# LM502_Break_Out_Board_v1_0.net
KiCad netlist of a schematic drawn in EAGLE
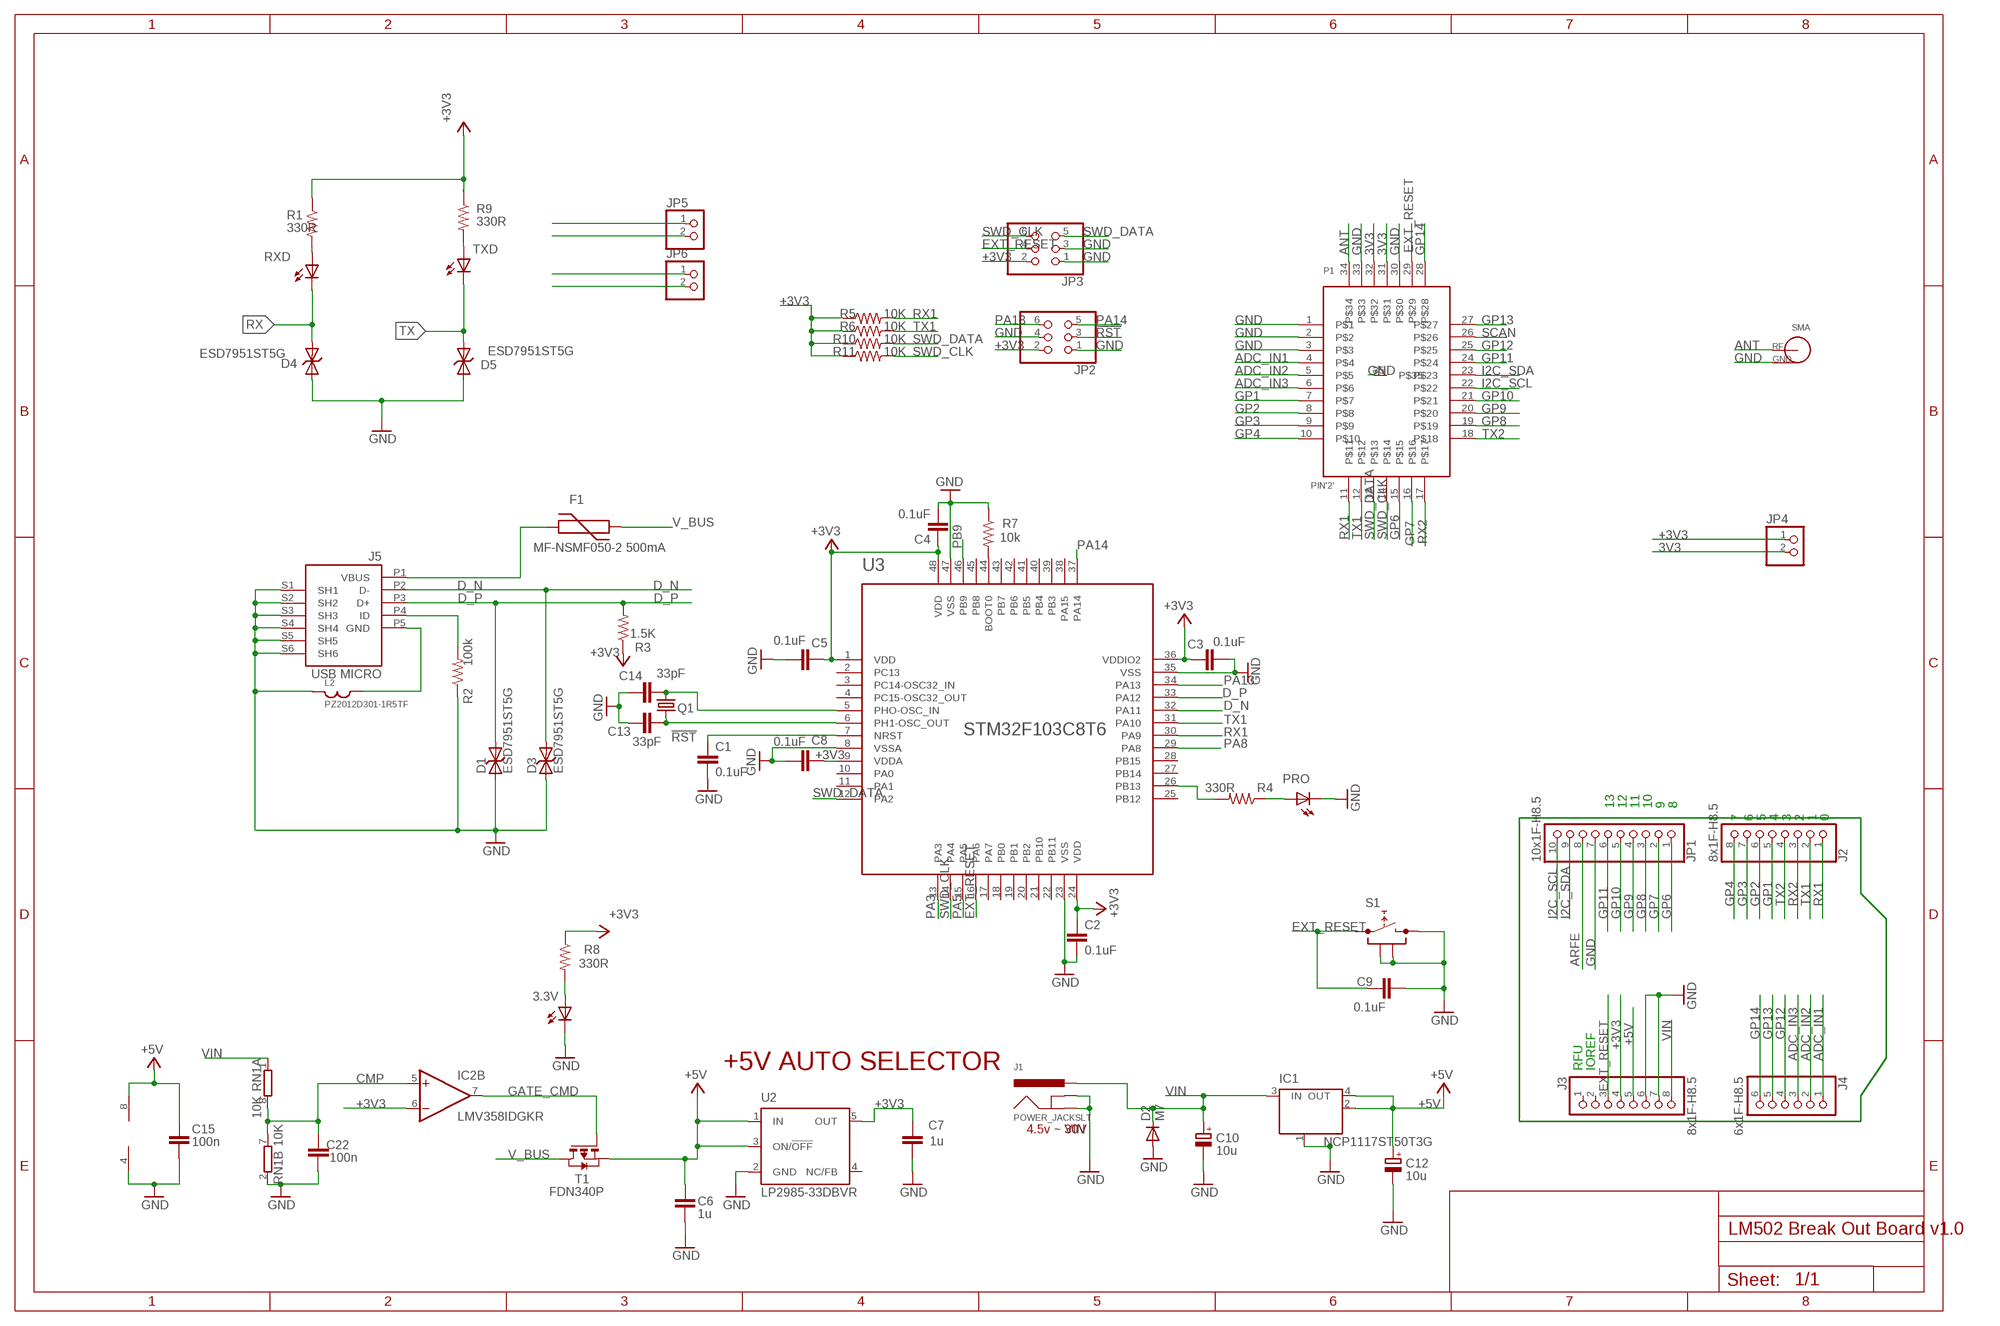
[diagram p0: schematic, sheet 1]

(export (version "E")
  (design (tool "Eeschema 10.0.6"))
  (components
    (comp (ref "3.3V")
      (value "LEDCHIP-LED0603")
      (footprint "eagle-import:CHIP-LED0603")
      (libsource (lib "eagle-import") (part "LEDCHIP-LED0603"))
    )
    (comp (ref "C1")
      (value "0.1uF")
      (footprint "eagle-import:C0402")
      (libsource (lib "eagle-import") (part "dragino-passive_C-EUC0402"))
    )
    (comp (ref "C2")
      (value "0.1uF")
      (footprint "eagle-import:C0402")
      (libsource (lib "eagle-import") (part "dragino-passive_C-EUC0402"))
    )
    (comp (ref "C3")
      (value "0.1uF")
      (footprint "eagle-import:C0402")
      (libsource (lib "eagle-import") (part "dragino-passive_C-EUC0402"))
    )
    (comp (ref "C4")
      (value "0.1uF")
      (footprint "eagle-import:C0402")
      (libsource (lib "eagle-import") (part "dragino-passive_C-EUC0402"))
    )
    (comp (ref "C5")
      (value "0.1uF")
      (footprint "eagle-import:C0402")
      (libsource (lib "eagle-import") (part "dragino-passive_C-EUC0402"))
    )
    (comp (ref "C6")
      (value "1u")
      (footprint "eagle-import:C0603-ROUND")
      (libsource (lib "eagle-import") (part "C-EUC0603"))
    )
    (comp (ref "C7")
      (value "1u")
      (footprint "eagle-import:C0603-ROUND")
      (libsource (lib "eagle-import") (part "C-EUC0603"))
    )
    (comp (ref "C8")
      (value "0.1uF")
      (footprint "eagle-import:C0402")
      (libsource (lib "eagle-import") (part "dragino-passive_C-EUC0402"))
    )
    (comp (ref "C9")
      (value "0.1uF")
      (footprint "eagle-import:C0402")
      (libsource (lib "eagle-import") (part "dragino-passive_C-EUC0402"))
    )
    (comp (ref "C10")
      (value "10u")
      (footprint "eagle-import:SMC_B")
      (libsource (lib "eagle-import") (part "CPOL-EUSMCB"))
    )
    (comp (ref "C12")
      (value "10u")
      (footprint "eagle-import:SMC_B")
      (libsource (lib "eagle-import") (part "CPOL-EUSMCB"))
    )
    (comp (ref "C13")
      (value "33pF")
      (footprint "eagle-import:C0402")
      (libsource (lib "eagle-import") (part "dragino-passive_C-EUC0402"))
    )
    (comp (ref "C14")
      (value "33pF")
      (footprint "eagle-import:C0402")
      (libsource (lib "eagle-import") (part "dragino-passive_C-EUC0402"))
    )
    (comp (ref "C15")
      (value "100n")
      (footprint "eagle-import:C0402")
      (libsource (lib "eagle-import") (part "C-EUC0402"))
    )
    (comp (ref "C22")
      (value "100n")
      (footprint "eagle-import:C0402")
      (libsource (lib "eagle-import") (part "C-EUC0402"))
    )
    (comp (ref "D1")
      (value "ESD7951ST5G")
      (footprint "eagle-import:SOD−923")
      (libsource (lib "eagle-import") (part "TVSSOD−923"))
    )
    (comp (ref "D2")
      (value "M7")
      (footprint "eagle-import:SMB")
      (libsource (lib "eagle-import") (part "DIODE-SMB"))
    )
    (comp (ref "D3")
      (value "ESD7951ST5G")
      (footprint "eagle-import:SOD−923")
      (libsource (lib "eagle-import") (part "TVSSOD−923"))
    )
    (comp (ref "D4")
      (value "ESD7951ST5G")
      (footprint "eagle-import:SOD−923")
      (libsource (lib "eagle-import") (part "TVSSOD−923"))
    )
    (comp (ref "D5")
      (value "ESD7951ST5G")
      (footprint "eagle-import:SOD−923")
      (libsource (lib "eagle-import") (part "TVSSOD−923"))
    )
    (comp (ref "F1")
      (value "MF-NSMF050-2 500mA")
      (footprint "eagle-import:R1206")
      (libsource (lib "eagle-import") (part "FUSE1206"))
    )
    (comp (ref "IC1")
      (value "NCP1117ST50T3G")
      (footprint "eagle-import:SOT223")
      (libsource (lib "eagle-import") (part "MC33269ST-3.3T3"))
    )
    (comp (ref "IC2")
      (value "LMV358IDGKR")
      (footprint "eagle-import:MSOP08")
      (libsource (lib "eagle-import") (part "LMV358?MMX"))
    )
    (comp (ref "J1")
      (value "POWER_JACKSLT")
      (footprint "eagle-import:POWER_JACK_SLOT")
      (libsource (lib "eagle-import") (part "POWER_JACKSLT"))
    )
    (comp (ref "J2")
      (value "8x1F-H8.5")
      (footprint "eagle-import:1X08")
      (libsource (lib "eagle-import") (part "PINHD-1X8"))
    )
    (comp (ref "J3")
      (value "8x1F-H8.5")
      (footprint "eagle-import:1X08")
      (libsource (lib "eagle-import") (part "PINHD-1X8"))
    )
    (comp (ref "J4")
      (value "6x1F-H8.5")
      (footprint "eagle-import:1X06")
      (libsource (lib "eagle-import") (part "PINHD-1X6"))
    )
    (comp (ref "J5")
      (value "USB MICRO")
      (footprint "eagle-import:CON2_USB_MICRO_B_AT")
      (libsource (lib "eagle-import") (part "MYCON2_USB-MINI-B"))
    )
    (comp (ref "JP1")
      (value "10x1F-H8.5")
      (footprint "eagle-import:1X10")
      (libsource (lib "eagle-import") (part "PINHD-1X10"))
    )
    (comp (ref "JP2")
      (value "PINHD-2X3")
      (footprint "eagle-import:2X3-2.0")
      (libsource (lib "eagle-import") (part "PINHD-2X3"))
    )
    (comp (ref "JP3")
      (value "PINHD-2X3'2'")
      (footprint "eagle-import:2X03")
      (libsource (lib "eagle-import") (part "PINHD-2X3'2'"))
    )
    (comp (ref "JP4")
      (value "PINHD-1X2")
      (footprint "eagle-import:1X02")
      (libsource (lib "eagle-import") (part "PINHD-1X2"))
    )
    (comp (ref "JP5")
      (value "PINHD-1X2")
      (footprint "eagle-import:1X02")
      (libsource (lib "eagle-import") (part "PINHD-1X2"))
    )
    (comp (ref "JP6")
      (value "PINHD-1X2")
      (footprint "eagle-import:1X02")
      (libsource (lib "eagle-import") (part "PINHD-1X2"))
    )
    (comp (ref "L2")
      (value "PZ2012D301-1R5TF")
      (footprint "eagle-import:C0805@1")
      (libsource (lib "eagle-import") (part "BEADS0805"))
    )
    (comp (ref "P1")
      (value "PIN'2'")
      (footprint "eagle-import:LM502")
      (libsource (lib "eagle-import") (part "PIN'2'"))
    )
    (comp (ref "PRO")
      (value "LEDCHIP-LED0603")
      (footprint "eagle-import:CHIP-LED0603")
      (libsource (lib "eagle-import") (part "LEDCHIP-LED0603"))
    )
    (comp (ref "Q1")
      (value "CRYSTALHC49S")
      (footprint "eagle-import:HC49_S")
      (libsource (lib "eagle-import") (part "CRYSTALHC49S"))
    )
    (comp (ref "R1")
      (value "330R")
      (footprint "eagle-import:R0402")
      (libsource (lib "eagle-import") (part "R-US_R0402"))
    )
    (comp (ref "R2")
      (value "100k")
      (footprint "eagle-import:R0402")
      (libsource (lib "eagle-import") (part "R-US_R0402"))
    )
    (comp (ref "R3")
      (value "1.5K")
      (footprint "eagle-import:R0402")
      (libsource (lib "eagle-import") (part "R-US_R0402"))
    )
    (comp (ref "R4")
      (value "330R")
      (footprint "eagle-import:R0402")
      (libsource (lib "eagle-import") (part "R-US_R0402"))
    )
    (comp (ref "R5")
      (value "10K")
      (footprint "eagle-import:R0402")
      (libsource (lib "eagle-import") (part "R-US_R0402"))
    )
    (comp (ref "R6")
      (value "10K")
      (footprint "eagle-import:R0402")
      (libsource (lib "eagle-import") (part "R-US_R0402"))
    )
    (comp (ref "R7")
      (value "10k")
      (footprint "eagle-import:R0402")
      (libsource (lib "eagle-import") (part "R-US_R0402"))
    )
    (comp (ref "R8")
      (value "330R")
      (footprint "eagle-import:R0402")
      (libsource (lib "eagle-import") (part "R-US_R0402"))
    )
    (comp (ref "R9")
      (value "330R")
      (footprint "eagle-import:R0402")
      (libsource (lib "eagle-import") (part "R-US_R0402"))
    )
    (comp (ref "R10")
      (value "10K")
      (footprint "eagle-import:R0402")
      (libsource (lib "eagle-import") (part "R-US_R0402"))
    )
    (comp (ref "R11")
      (value "10K")
      (footprint "eagle-import:R0402")
      (libsource (lib "eagle-import") (part "R-US_R0402"))
    )
    (comp (ref "RN1")
      (value "10K")
      (footprint "eagle-import:CAY16")
      (libsource (lib "eagle-import") (part "4R-NCAY16"))
    )
    (comp (ref "RXD")
      (value "LEDCHIP-LED0603")
      (footprint "eagle-import:CHIP-LED0603")
      (libsource (lib "eagle-import") (part "LEDCHIP-LED0603"))
    )
    (comp (ref "S1")
      (value "PUSH_SWITCH")
      (footprint "eagle-import:SWITCH_6X6X5")
      (libsource (lib "eagle-import") (part "PUSH_SWITCH"))
    )
    (comp (ref "SMA")
      (value "SMA-KWE")
      (footprint "eagle-import:SMA-KWE")
      (libsource (lib "eagle-import") (part "SMA-KWE"))
    )
    (comp (ref "T1")
      (value "FDN340P")
      (footprint "eagle-import:SOT-23")
      (libsource (lib "eagle-import") (part "PMOSSOT23"))
    )
    (comp (ref "TXD")
      (value "LEDCHIP-LED0603")
      (footprint "eagle-import:CHIP-LED0603")
      (libsource (lib "eagle-import") (part "LEDCHIP-LED0603"))
    )
    (comp (ref "U2")
      (value "LP2985-33DBVR")
      (footprint "eagle-import:SOT23-DBV")
      (libsource (lib "eagle-import") (part "LP2985-XXDBVR33"))
    )
    (comp (ref "U3")
      (value "STM32F103C8T6")
      (footprint "eagle-import:LQFP48")
      (libsource (lib "eagle-import") (part "STM32L0XX"))
    )
  )
  (nets
    (net (code "1") (name "+3V3") (class "Default")
      (node (ref "C2") (pin "1") (pinfunction "1_1") (pintype "passive"))
      (node (ref "C3") (pin "1") (pinfunction "1_1") (pintype "passive"))
      (node (ref "C4") (pin "1") (pinfunction "1_1") (pintype "passive"))
      (node (ref "C5") (pin "1") (pinfunction "1_1") (pintype "passive"))
      (node (ref "C7") (pin "2") (pinfunction "2_2") (pintype "passive"))
      (node (ref "C8") (pin "1") (pinfunction "1_1") (pintype "passive"))
      (node (ref "IC2") (pin "6") (pinfunction "-IN_6") (pintype "input"))
      (node (ref "J3") (pin "4") (pinfunction "4_4") (pintype "passive"))
      (node (ref "JP2") (pin "2") (pinfunction "2_2") (pintype "passive"))
      (node (ref "JP3") (pin "2") (pinfunction "2_2") (pintype "passive"))
      (node (ref "JP4") (pin "1") (pinfunction "1_1") (pintype "passive"))
      (node (ref "R1") (pin "1") (pinfunction "1_1") (pintype "passive"))
      (node (ref "R10") (pin "1") (pinfunction "1_1") (pintype "passive"))
      (node (ref "R11") (pin "1") (pinfunction "1_1") (pintype "passive"))
      (node (ref "R3") (pin "1") (pinfunction "1_1") (pintype "passive"))
      (node (ref "R5") (pin "1") (pinfunction "1_1") (pintype "passive"))
      (node (ref "R6") (pin "1") (pinfunction "1_1") (pintype "passive"))
      (node (ref "R8") (pin "1") (pinfunction "1_1") (pintype "passive"))
      (node (ref "R9") (pin "1") (pinfunction "1_1") (pintype "passive"))
      (node (ref "U2") (pin "5") (pinfunction "OUT_5") (pintype "passive"))
      (node (ref "U3") (pin "1") (pinfunction "VDD_1") (pintype "bidirectional"))
      (node (ref "U3") (pin "24") (pinfunction "VDD_24") (pintype "bidirectional"))
      (node (ref "U3") (pin "36") (pinfunction "VDDIO2_36") (pintype "bidirectional"))
      (node (ref "U3") (pin "48") (pinfunction "VDD_48") (pintype "bidirectional"))
      (node (ref "U3") (pin "9") (pinfunction "VDDA_9") (pintype "bidirectional"))
    )
    (net (code "2") (name "+5V") (class "Default")
      (node (ref "C12") (pin "+") (pinfunction "+_+") (pintype "passive"))
      (node (ref "C15") (pin "1") (pinfunction "1_1") (pintype "passive"))
      (node (ref "C6") (pin "2") (pinfunction "2_2") (pintype "passive"))
      (node (ref "IC1") (pin "2") (pinfunction "OUT_2") (pintype "passive"))
      (node (ref "IC1") (pin "4") (pinfunction "OUT_4") (pintype "passive"))
      (node (ref "IC2") (pin "8") (pinfunction "V+_8") (pintype "power_in"))
      (node (ref "J3") (pin "5") (pinfunction "5_5") (pintype "passive"))
      (node (ref "T1") (pin "2") (pinfunction "S_2") (pintype "passive"))
      (node (ref "U2") (pin "1") (pinfunction "IN_1") (pintype "input"))
      (node (ref "U2") (pin "3") (pinfunction "ON/~{OFF}_3") (pintype "input"))
    )
    (net (code "3") (name "/3V3") (class "Default")
      (node (ref "JP4") (pin "2") (pinfunction "2_2") (pintype "passive"))
      (node (ref "P1") (pin "31") (pinfunction "P$31_31") (pintype "bidirectional"))
      (node (ref "P1") (pin "32") (pinfunction "P$32_32") (pintype "bidirectional"))
    )
    (net (code "4") (name "/ADC_IN1") (class "Default")
      (node (ref "J4") (pin "1") (pinfunction "1_1") (pintype "passive"))
      (node (ref "P1") (pin "4") (pinfunction "P$4_4") (pintype "bidirectional"))
    )
    (net (code "5") (name "/ADC_IN2") (class "Default")
      (node (ref "J4") (pin "2") (pinfunction "2_2") (pintype "passive"))
      (node (ref "P1") (pin "5") (pinfunction "P$5_5") (pintype "bidirectional"))
    )
    (net (code "6") (name "/ADC_IN3") (class "Default")
      (node (ref "J4") (pin "3") (pinfunction "3_3") (pintype "passive"))
      (node (ref "P1") (pin "6") (pinfunction "P$6_6") (pintype "bidirectional"))
    )
    (net (code "7") (name "/ANT") (class "Default")
      (node (ref "P1") (pin "34") (pinfunction "P$34_34") (pintype "bidirectional"))
      (node (ref "SMA") (pin "1") (pinfunction "SIG_1") (pintype "passive"))
    )
    (net (code "8") (name "/ARFE") (class "Default")
      (node (ref "JP1") (pin "8") (pinfunction "8_8") (pintype "passive"))
    )
    (net (code "9") (name "/CMP") (class "Default")
      (node (ref "C22") (pin "2") (pinfunction "2_2") (pintype "passive"))
      (node (ref "IC2") (pin "5") (pinfunction "+IN_5") (pintype "input"))
      (node (ref "RN1") (pin "7") (pinfunction "2_7") (pintype "passive"))
      (node (ref "RN1") (pin "8") (pinfunction "2_8") (pintype "passive"))
    )
    (net (code "10") (name "/D_N") (class "Default")
      (node (ref "D3") (pin "P$2") (pinfunction "2_P$2") (pintype "passive"))
      (node (ref "J5") (pin "P2") (pinfunction "D-_P2") (pintype "bidirectional"))
      (node (ref "U3") (pin "32") (pinfunction "PA11_32") (pintype "bidirectional"))
    )
    (net (code "11") (name "/D_P") (class "Default")
      (node (ref "D1") (pin "P$2") (pinfunction "2_P$2") (pintype "passive"))
      (node (ref "J5") (pin "P3") (pinfunction "D+_P3") (pintype "bidirectional"))
      (node (ref "R3") (pin "2") (pinfunction "2_2") (pintype "passive"))
      (node (ref "U3") (pin "33") (pinfunction "PA12_33") (pintype "bidirectional"))
    )
    (net (code "12") (name "/EXT_RESET") (class "Default")
      (node (ref "C9") (pin "1") (pinfunction "1_1") (pintype "passive"))
      (node (ref "J3") (pin "3") (pinfunction "3_3") (pintype "passive"))
      (node (ref "JP3") (pin "4") (pinfunction "4_4") (pintype "passive"))
      (node (ref "P1") (pin "29") (pinfunction "P$29_29") (pintype "bidirectional"))
      (node (ref "S1") (pin "1") (pinfunction "1_1") (pintype "passive"))
      (node (ref "U3") (pin "16") (pinfunction "PA6_16") (pintype "bidirectional"))
    )
    (net (code "13") (name "/GATE_CMD") (class "Default")
      (node (ref "IC2") (pin "7") (pinfunction "OUT_7") (pintype "output"))
      (node (ref "T1") (pin "3") (pinfunction "G_3") (pintype "passive"))
    )
    (net (code "14") (name "/GP1") (class "Default")
      (node (ref "J2") (pin "5") (pinfunction "5_5") (pintype "passive"))
      (node (ref "P1") (pin "7") (pinfunction "P$7_7") (pintype "bidirectional"))
    )
    (net (code "15") (name "/GP2") (class "Default")
      (node (ref "J2") (pin "6") (pinfunction "6_6") (pintype "passive"))
      (node (ref "P1") (pin "8") (pinfunction "P$8_8") (pintype "bidirectional"))
    )
    (net (code "16") (name "/GP3") (class "Default")
      (node (ref "J2") (pin "7") (pinfunction "7_7") (pintype "passive"))
      (node (ref "P1") (pin "9") (pinfunction "P$9_9") (pintype "bidirectional"))
    )
    (net (code "17") (name "/GP4") (class "Default")
      (node (ref "J2") (pin "8") (pinfunction "8_8") (pintype "passive"))
      (node (ref "P1") (pin "10") (pinfunction "P$10_10") (pintype "bidirectional"))
    )
    (net (code "18") (name "/GP6") (class "Default")
      (node (ref "JP1") (pin "1") (pinfunction "1_1") (pintype "passive"))
      (node (ref "P1") (pin "15") (pinfunction "P$15_15") (pintype "bidirectional"))
    )
    (net (code "19") (name "/GP7") (class "Default")
      (node (ref "JP1") (pin "2") (pinfunction "2_2") (pintype "passive"))
      (node (ref "P1") (pin "16") (pinfunction "P$16_16") (pintype "bidirectional"))
    )
    (net (code "20") (name "/GP8") (class "Default")
      (node (ref "JP1") (pin "3") (pinfunction "3_3") (pintype "passive"))
      (node (ref "P1") (pin "19") (pinfunction "P$19_19") (pintype "bidirectional"))
    )
    (net (code "21") (name "/GP9") (class "Default")
      (node (ref "JP1") (pin "4") (pinfunction "4_4") (pintype "passive"))
      (node (ref "P1") (pin "20") (pinfunction "P$20_20") (pintype "bidirectional"))
    )
    (net (code "22") (name "/GP10") (class "Default")
      (node (ref "JP1") (pin "5") (pinfunction "5_5") (pintype "passive"))
      (node (ref "P1") (pin "21") (pinfunction "P$21_21") (pintype "bidirectional"))
    )
    (net (code "23") (name "/GP11") (class "Default")
      (node (ref "JP1") (pin "6") (pinfunction "6_6") (pintype "passive"))
      (node (ref "P1") (pin "24") (pinfunction "P$24_24") (pintype "bidirectional"))
    )
    (net (code "24") (name "/GP12") (class "Default")
      (node (ref "J4") (pin "4") (pinfunction "4_4") (pintype "passive"))
      (node (ref "P1") (pin "25") (pinfunction "P$25_25") (pintype "bidirectional"))
    )
    (net (code "25") (name "/GP13") (class "Default")
      (node (ref "J4") (pin "5") (pinfunction "5_5") (pintype "passive"))
      (node (ref "P1") (pin "27") (pinfunction "P$27_27") (pintype "bidirectional"))
    )
    (net (code "26") (name "/GP14") (class "Default")
      (node (ref "J4") (pin "6") (pinfunction "6_6") (pintype "passive"))
      (node (ref "P1") (pin "28") (pinfunction "P$28_28") (pintype "bidirectional"))
    )
    (net (code "27") (name "/I2C_SCL") (class "Default")
      (node (ref "JP1") (pin "10") (pinfunction "10_10") (pintype "passive"))
      (node (ref "P1") (pin "22") (pinfunction "P$22_22") (pintype "bidirectional"))
    )
    (net (code "28") (name "/I2C_SDA") (class "Default")
      (node (ref "JP1") (pin "9") (pinfunction "9_9") (pintype "passive"))
      (node (ref "P1") (pin "23") (pinfunction "P$23_23") (pintype "bidirectional"))
    )
    (net (code "29") (name "/PA3") (class "Default")
      (node (ref "U3") (pin "13") (pinfunction "PA3_13") (pintype "bidirectional"))
    )
    (net (code "30") (name "/PA5") (class "Default")
      (node (ref "U3") (pin "15") (pinfunction "PA5_15") (pintype "bidirectional"))
    )
    (net (code "31") (name "/PA8") (class "Default")
      (node (ref "U3") (pin "29") (pinfunction "PA8_29") (pintype "bidirectional"))
    )
    (net (code "32") (name "/PA13") (class "Default")
      (node (ref "JP2") (pin "6") (pinfunction "6_6") (pintype "passive"))
      (node (ref "U3") (pin "34") (pinfunction "PA13_34") (pintype "bidirectional"))
    )
    (net (code "33") (name "/PA14") (class "Default")
      (node (ref "JP2") (pin "5") (pinfunction "5_5") (pintype "passive"))
      (node (ref "U3") (pin "37") (pinfunction "PA14_37") (pintype "bidirectional"))
    )
    (net (code "34") (name "/PB9") (class "Default")
      (node (ref "U3") (pin "46") (pinfunction "PB9_46") (pintype "bidirectional"))
    )
    (net (code "35") (name "/RX1") (class "Default")
      (node (ref "J2") (pin "1") (pinfunction "1_1") (pintype "passive"))
      (node (ref "JP5") (pin "2") (pinfunction "2_2") (pintype "passive"))
      (node (ref "P1") (pin "11") (pinfunction "P$11_11") (pintype "bidirectional"))
      (node (ref "R5") (pin "2") (pinfunction "2_2") (pintype "passive"))
      (node (ref "U3") (pin "30") (pinfunction "PA9_30") (pintype "bidirectional"))
    )
    (net (code "36") (name "/RX2") (class "Default")
      (node (ref "J2") (pin "3") (pinfunction "3_3") (pintype "passive"))
      (node (ref "P1") (pin "17") (pinfunction "P$17_17") (pintype "bidirectional"))
    )
    (net (code "37") (name "/SCAN") (class "Default")
      (node (ref "P1") (pin "26") (pinfunction "P$26_26") (pintype "bidirectional"))
    )
    (net (code "38") (name "/SWD_CLK") (class "Default")
      (node (ref "JP3") (pin "6") (pinfunction "6_6") (pintype "passive"))
      (node (ref "P1") (pin "14") (pinfunction "P$14_14") (pintype "bidirectional"))
      (node (ref "R11") (pin "2") (pinfunction "2_2") (pintype "passive"))
      (node (ref "U3") (pin "14") (pinfunction "PA4_14") (pintype "bidirectional"))
    )
    (net (code "39") (name "/SWD_DATA") (class "Default")
      (node (ref "JP3") (pin "5") (pinfunction "5_5") (pintype "passive"))
      (node (ref "P1") (pin "13") (pinfunction "P$13_13") (pintype "bidirectional"))
      (node (ref "R10") (pin "2") (pinfunction "2_2") (pintype "passive"))
      (node (ref "U3") (pin "12") (pinfunction "PA2_12") (pintype "bidirectional"))
    )
    (net (code "40") (name "/TX1") (class "Default")
      (node (ref "J2") (pin "2") (pinfunction "2_2") (pintype "passive"))
      (node (ref "JP6") (pin "1") (pinfunction "1_1") (pintype "passive"))
      (node (ref "P1") (pin "12") (pinfunction "P$12_12") (pintype "bidirectional"))
      (node (ref "R6") (pin "2") (pinfunction "2_2") (pintype "passive"))
      (node (ref "U3") (pin "31") (pinfunction "PA10_31") (pintype "bidirectional"))
    )
    (net (code "41") (name "/TX2") (class "Default")
      (node (ref "J2") (pin "4") (pinfunction "4_4") (pintype "passive"))
      (node (ref "P1") (pin "18") (pinfunction "P$18_18") (pintype "bidirectional"))
    )
    (net (code "42") (name "/VIN") (class "Default")
      (node (ref "C10") (pin "+") (pinfunction "+_+") (pintype "passive"))
      (node (ref "D2") (pin "C") (pinfunction "C_C") (pintype "passive"))
      (node (ref "IC1") (pin "3") (pinfunction "IN_3") (pintype "input"))
      (node (ref "J1") (pin "PWR") (pinfunction "PWR_PWR") (pintype "bidirectional"))
      (node (ref "J3") (pin "8") (pinfunction "8_8") (pintype "passive"))
      (node (ref "RN1") (pin "1") (pinfunction "1_1") (pintype "passive"))
    )
    (net (code "43") (name "/V_BUS") (class "Default")
      (node (ref "F1") (pin "1") (pinfunction "1_1") (pintype "passive"))
      (node (ref "T1") (pin "1") (pinfunction "D_1") (pintype "passive"))
    )
    (net (code "44") (name "/~{RST}") (class "Default")
      (node (ref "C1") (pin "1") (pinfunction "1_1") (pintype "passive"))
      (node (ref "JP2") (pin "3") (pinfunction "3_3") (pintype "passive"))
      (node (ref "U3") (pin "7") (pinfunction "NRST_7") (pintype "bidirectional"))
    )
    (net (code "45") (name "GND") (class "Default")
      (node (ref "3.3V") (pin "C") (pinfunction "C_C") (pintype "passive"))
      (node (ref "C1") (pin "2") (pinfunction "2_2") (pintype "passive"))
      (node (ref "C10") (pin "-") (pinfunction "-_-") (pintype "passive"))
      (node (ref "C12") (pin "-") (pinfunction "-_-") (pintype "passive"))
      (node (ref "C13") (pin "1") (pinfunction "1_1") (pintype "passive"))
      (node (ref "C14") (pin "1") (pinfunction "1_1") (pintype "passive"))
      (node (ref "C15") (pin "2") (pinfunction "2_2") (pintype "passive"))
      (node (ref "C2") (pin "2") (pinfunction "2_2") (pintype "passive"))
      (node (ref "C22") (pin "1") (pinfunction "1_1") (pintype "passive"))
      (node (ref "C3") (pin "2") (pinfunction "2_2") (pintype "passive"))
      (node (ref "C4") (pin "2") (pinfunction "2_2") (pintype "passive"))
      (node (ref "C5") (pin "2") (pinfunction "2_2") (pintype "passive"))
      (node (ref "C6") (pin "1") (pinfunction "1_1") (pintype "passive"))
      (node (ref "C7") (pin "1") (pinfunction "1_1") (pintype "passive"))
      (node (ref "C8") (pin "2") (pinfunction "2_2") (pintype "passive"))
      (node (ref "C9") (pin "2") (pinfunction "2_2") (pintype "passive"))
      (node (ref "D1") (pin "P$1") (pinfunction "1_P$1") (pintype "passive"))
      (node (ref "D2") (pin "A") (pinfunction "A_A") (pintype "passive"))
      (node (ref "D3") (pin "P$1") (pinfunction "1_P$1") (pintype "passive"))
      (node (ref "D4") (pin "P$1") (pinfunction "1_P$1") (pintype "passive"))
      (node (ref "D5") (pin "P$1") (pinfunction "1_P$1") (pintype "passive"))
      (node (ref "IC1") (pin "1") (pinfunction "GND/ADJ_1") (pintype "input"))
      (node (ref "IC2") (pin "4") (pinfunction "V-_4") (pintype "power_in"))
      (node (ref "J1") (pin "GND@1") (pinfunction "GNDBREAK_GND@1") (pintype "bidirectional"))
      (node (ref "J1") (pin "GND@2") (pinfunction "GND_GND@2") (pintype "bidirectional"))
      (node (ref "J3") (pin "6") (pinfunction "6_6") (pintype "passive"))
      (node (ref "J3") (pin "7") (pinfunction "7_7") (pintype "passive"))
      (node (ref "J5") (pin "S1") (pinfunction "SH1_S1") (pintype "passive"))
      (node (ref "J5") (pin "S2") (pinfunction "SH2_S2") (pintype "passive"))
      (node (ref "J5") (pin "S3") (pinfunction "SH3_S3") (pintype "passive"))
      (node (ref "J5") (pin "S4") (pinfunction "SH4_S4") (pintype "passive"))
      (node (ref "J5") (pin "S5") (pinfunction "SH5_S5") (pintype "passive"))
      (node (ref "J5") (pin "S6") (pinfunction "SH6_S6") (pintype "passive"))
      (node (ref "JP1") (pin "7") (pinfunction "7_7") (pintype "passive"))
      (node (ref "JP2") (pin "1") (pinfunction "1_1") (pintype "passive"))
      (node (ref "JP2") (pin "4") (pinfunction "4_4") (pintype "passive"))
      (node (ref "JP3") (pin "1") (pinfunction "1_1") (pintype "passive"))
      (node (ref "JP3") (pin "3") (pinfunction "3_3") (pintype "passive"))
      (node (ref "L2") (pin "1") (pinfunction "P$1_1") (pintype "bidirectional"))
      (node (ref "P1") (pin "1") (pinfunction "P$1_1") (pintype "bidirectional"))
      (node (ref "P1") (pin "2") (pinfunction "P$2_2") (pintype "bidirectional"))
      (node (ref "P1") (pin "3") (pinfunction "P$3_3") (pintype "bidirectional"))
      (node (ref "P1") (pin "30") (pinfunction "P$30_30") (pintype "bidirectional"))
      (node (ref "P1") (pin "33") (pinfunction "P$33_33") (pintype "bidirectional"))
      (node (ref "P1") (pin "35") (pinfunction "P$35_35") (pintype "bidirectional"))
      (node (ref "PRO") (pin "C") (pinfunction "C_C") (pintype "passive"))
      (node (ref "R2") (pin "1") (pinfunction "1_1") (pintype "passive"))
      (node (ref "R7") (pin "1") (pinfunction "1_1") (pintype "passive"))
      (node (ref "RN1") (pin "2") (pinfunction "1_2") (pintype "passive"))
      (node (ref "S1") (pin "2") (pinfunction "2_2") (pintype "passive"))
      (node (ref "S1") (pin "3") (pinfunction "3_3") (pintype "passive"))
      (node (ref "S1") (pin "4") (pinfunction "4_4") (pintype "passive"))
      (node (ref "SMA") (pin "2") (pinfunction "GND_2") (pintype "passive"))
      (node (ref "SMA") (pin "3") (pinfunction "GND_3") (pintype "passive"))
      (node (ref "SMA") (pin "4") (pinfunction "GND_4") (pintype "passive"))
      (node (ref "SMA") (pin "5") (pinfunction "GND_5") (pintype "passive"))
      (node (ref "U2") (pin "2") (pinfunction "GND_2") (pintype "power_in"))
      (node (ref "U3") (pin "23") (pinfunction "VSS_23") (pintype "bidirectional"))
      (node (ref "U3") (pin "35") (pinfunction "VSS_35") (pintype "bidirectional"))
      (node (ref "U3") (pin "47") (pinfunction "VSS_47") (pintype "bidirectional"))
      (node (ref "U3") (pin "8") (pinfunction "VSSA_8") (pintype "bidirectional"))
    )
    (net (code "46") (name "Net-(3.3V-PadA)") (class "Default")
      (node (ref "3.3V") (pin "A") (pinfunction "A_A") (pintype "passive"))
      (node (ref "R8") (pin "2") (pinfunction "2_2") (pintype "passive"))
    )
    (net (code "47") (name "Net-(J5-GND)") (class "Default")
      (node (ref "J5") (pin "P5") (pinfunction "GND_P5") (pintype "passive"))
      (node (ref "L2") (pin "2") (pinfunction "P$2_2") (pintype "bidirectional"))
    )
    (net (code "48") (name "Net-(J5-ID)") (class "Default")
      (node (ref "J5") (pin "P4") (pinfunction "ID_P4") (pintype "bidirectional"))
      (node (ref "R2") (pin "2") (pinfunction "2_2") (pintype "passive"))
    )
    (net (code "49") (name "Net-(J5-VBUS)") (class "Default")
      (node (ref "F1") (pin "2") (pinfunction "2_2") (pintype "passive"))
      (node (ref "J5") (pin "P1") (pinfunction "VBUS_P1") (pintype "power_in"))
    )
    (net (code "50") (name "Net-(PRO-PadA)") (class "Default")
      (node (ref "PRO") (pin "A") (pinfunction "A_A") (pintype "passive"))
      (node (ref "R4") (pin "1") (pinfunction "1_1") (pintype "passive"))
    )
    (net (code "51") (name "Net-(R1-Pad2)") (class "Default")
      (node (ref "R1") (pin "2") (pinfunction "2_2") (pintype "passive"))
      (node (ref "RXD") (pin "A") (pinfunction "A_A") (pintype "passive"))
    )
    (net (code "52") (name "Net-(R9-Pad2)") (class "Default")
      (node (ref "R9") (pin "2") (pinfunction "2_2") (pintype "passive"))
      (node (ref "TXD") (pin "A") (pinfunction "A_A") (pintype "passive"))
    )
    (net (code "53") (name "Net-(U3-BOOT0)") (class "Default")
      (node (ref "R7") (pin "2") (pinfunction "2_2") (pintype "passive"))
      (node (ref "U3") (pin "44") (pinfunction "BOOT0_44") (pintype "bidirectional"))
    )
    (net (code "54") (name "Net-(U3-PB13)") (class "Default")
      (node (ref "R4") (pin "2") (pinfunction "2_2") (pintype "passive"))
      (node (ref "U3") (pin "26") (pinfunction "PB13_26") (pintype "bidirectional"))
    )
    (net (code "55") (name "Net-(U3-PH1-OSC_OUT)") (class "Default")
      (node (ref "C13") (pin "2") (pinfunction "2_2") (pintype "passive"))
      (node (ref "Q1") (pin "1") (pinfunction "1_1") (pintype "passive"))
      (node (ref "U3") (pin "6") (pinfunction "PH1-OSC_OUT_6") (pintype "bidirectional"))
    )
    (net (code "56") (name "Net-(U3-PHO-OSC_IN)") (class "Default")
      (node (ref "C14") (pin "2") (pinfunction "2_2") (pintype "passive"))
      (node (ref "Q1") (pin "2") (pinfunction "2_2") (pintype "passive"))
      (node (ref "U3") (pin "5") (pinfunction "PHO-OSC_IN_5") (pintype "bidirectional"))
    )
    (net (code "57") (name "RX") (class "Default")
      (node (ref "D4") (pin "P$2") (pinfunction "2_P$2") (pintype "passive"))
      (node (ref "JP5") (pin "1") (pinfunction "1_1") (pintype "passive"))
      (node (ref "RXD") (pin "C") (pinfunction "C_C") (pintype "passive"))
    )
    (net (code "58") (name "TX") (class "Default")
      (node (ref "D5") (pin "P$2") (pinfunction "2_P$2") (pintype "passive"))
      (node (ref "JP6") (pin "2") (pinfunction "2_2") (pintype "passive"))
      (node (ref "TXD") (pin "C") (pinfunction "C_C") (pintype "passive"))
    )
    (net (code "59") (name "unconnected-(J3-Pad1)") (class "Default")
      (node (ref "J3") (pin "1") (pinfunction "1_1") (pintype "passive"))
    )
    (net (code "60") (name "unconnected-(J3-Pad2)") (class "Default")
      (node (ref "J3") (pin "2") (pinfunction "2_2") (pintype "passive"))
    )
    (net (code "61") (name "unconnected-(U2-NC{slash}FB-Pad4)") (class "Default")
      (node (ref "U2") (pin "4") (pinfunction "NC/FB_4") (pintype "passive"))
    )
    (net (code "62") (name "unconnected-(U3-PA0-Pad10)") (class "Default")
      (node (ref "U3") (pin "10") (pinfunction "PA0_10") (pintype "bidirectional"))
    )
    (net (code "63") (name "unconnected-(U3-PA1-Pad11)") (class "Default")
      (node (ref "U3") (pin "11") (pinfunction "PA1_11") (pintype "bidirectional"))
    )
    (net (code "64") (name "unconnected-(U3-PA7-Pad17)") (class "Default")
      (node (ref "U3") (pin "17") (pinfunction "PA7_17") (pintype "bidirectional"))
    )
    (net (code "65") (name "unconnected-(U3-PA15-Pad38)") (class "Default")
      (node (ref "U3") (pin "38") (pinfunction "PA15_38") (pintype "bidirectional"))
    )
    (net (code "66") (name "unconnected-(U3-PB0-Pad18)") (class "Default")
      (node (ref "U3") (pin "18") (pinfunction "PB0_18") (pintype "bidirectional"))
    )
    (net (code "67") (name "unconnected-(U3-PB1-Pad19)") (class "Default")
      (node (ref "U3") (pin "19") (pinfunction "PB1_19") (pintype "bidirectional"))
    )
    (net (code "68") (name "unconnected-(U3-PB2-Pad20)") (class "Default")
      (node (ref "U3") (pin "20") (pinfunction "PB2_20") (pintype "bidirectional"))
    )
    (net (code "69") (name "unconnected-(U3-PB3-Pad39)") (class "Default")
      (node (ref "U3") (pin "39") (pinfunction "PB3_39") (pintype "bidirectional"))
    )
    (net (code "70") (name "unconnected-(U3-PB4-Pad40)") (class "Default")
      (node (ref "U3") (pin "40") (pinfunction "PB4_40") (pintype "bidirectional"))
    )
    (net (code "71") (name "unconnected-(U3-PB5-Pad41)") (class "Default")
      (node (ref "U3") (pin "41") (pinfunction "PB5_41") (pintype "bidirectional"))
    )
    (net (code "72") (name "unconnected-(U3-PB6-Pad42)") (class "Default")
      (node (ref "U3") (pin "42") (pinfunction "PB6_42") (pintype "bidirectional"))
    )
    (net (code "73") (name "unconnected-(U3-PB7-Pad43)") (class "Default")
      (node (ref "U3") (pin "43") (pinfunction "PB7_43") (pintype "bidirectional"))
    )
    (net (code "74") (name "unconnected-(U3-PB8-Pad45)") (class "Default")
      (node (ref "U3") (pin "45") (pinfunction "PB8_45") (pintype "bidirectional"))
    )
    (net (code "75") (name "unconnected-(U3-PB10-Pad21)") (class "Default")
      (node (ref "U3") (pin "21") (pinfunction "PB10_21") (pintype "bidirectional"))
    )
    (net (code "76") (name "unconnected-(U3-PB11-Pad22)") (class "Default")
      (node (ref "U3") (pin "22") (pinfunction "PB11_22") (pintype "bidirectional"))
    )
    (net (code "77") (name "unconnected-(U3-PB12-Pad25)") (class "Default")
      (node (ref "U3") (pin "25") (pinfunction "PB12_25") (pintype "bidirectional"))
    )
    (net (code "78") (name "unconnected-(U3-PB14-Pad27)") (class "Default")
      (node (ref "U3") (pin "27") (pinfunction "PB14_27") (pintype "bidirectional"))
    )
    (net (code "79") (name "unconnected-(U3-PB15-Pad28)") (class "Default")
      (node (ref "U3") (pin "28") (pinfunction "PB15_28") (pintype "bidirectional"))
    )
    (net (code "80") (name "unconnected-(U3-PC13-Pad2)") (class "Default")
      (node (ref "U3") (pin "2") (pinfunction "PC13_2") (pintype "bidirectional"))
    )
    (net (code "81") (name "unconnected-(U3-PC14-OSC32_IN-Pad3)") (class "Default")
      (node (ref "U3") (pin "3") (pinfunction "PC14-OSC32_IN_3") (pintype "bidirectional"))
    )
    (net (code "82") (name "unconnected-(U3-PC15-OSC32_OUT-Pad4)") (class "Default")
      (node (ref "U3") (pin "4") (pinfunction "PC15-OSC32_OUT_4") (pintype "bidirectional"))
    )
  )
)
